# Sensor_Module_0x02_Temperature_Humidity_.net
KiCad netlist of a schematic drawn in EAGLE
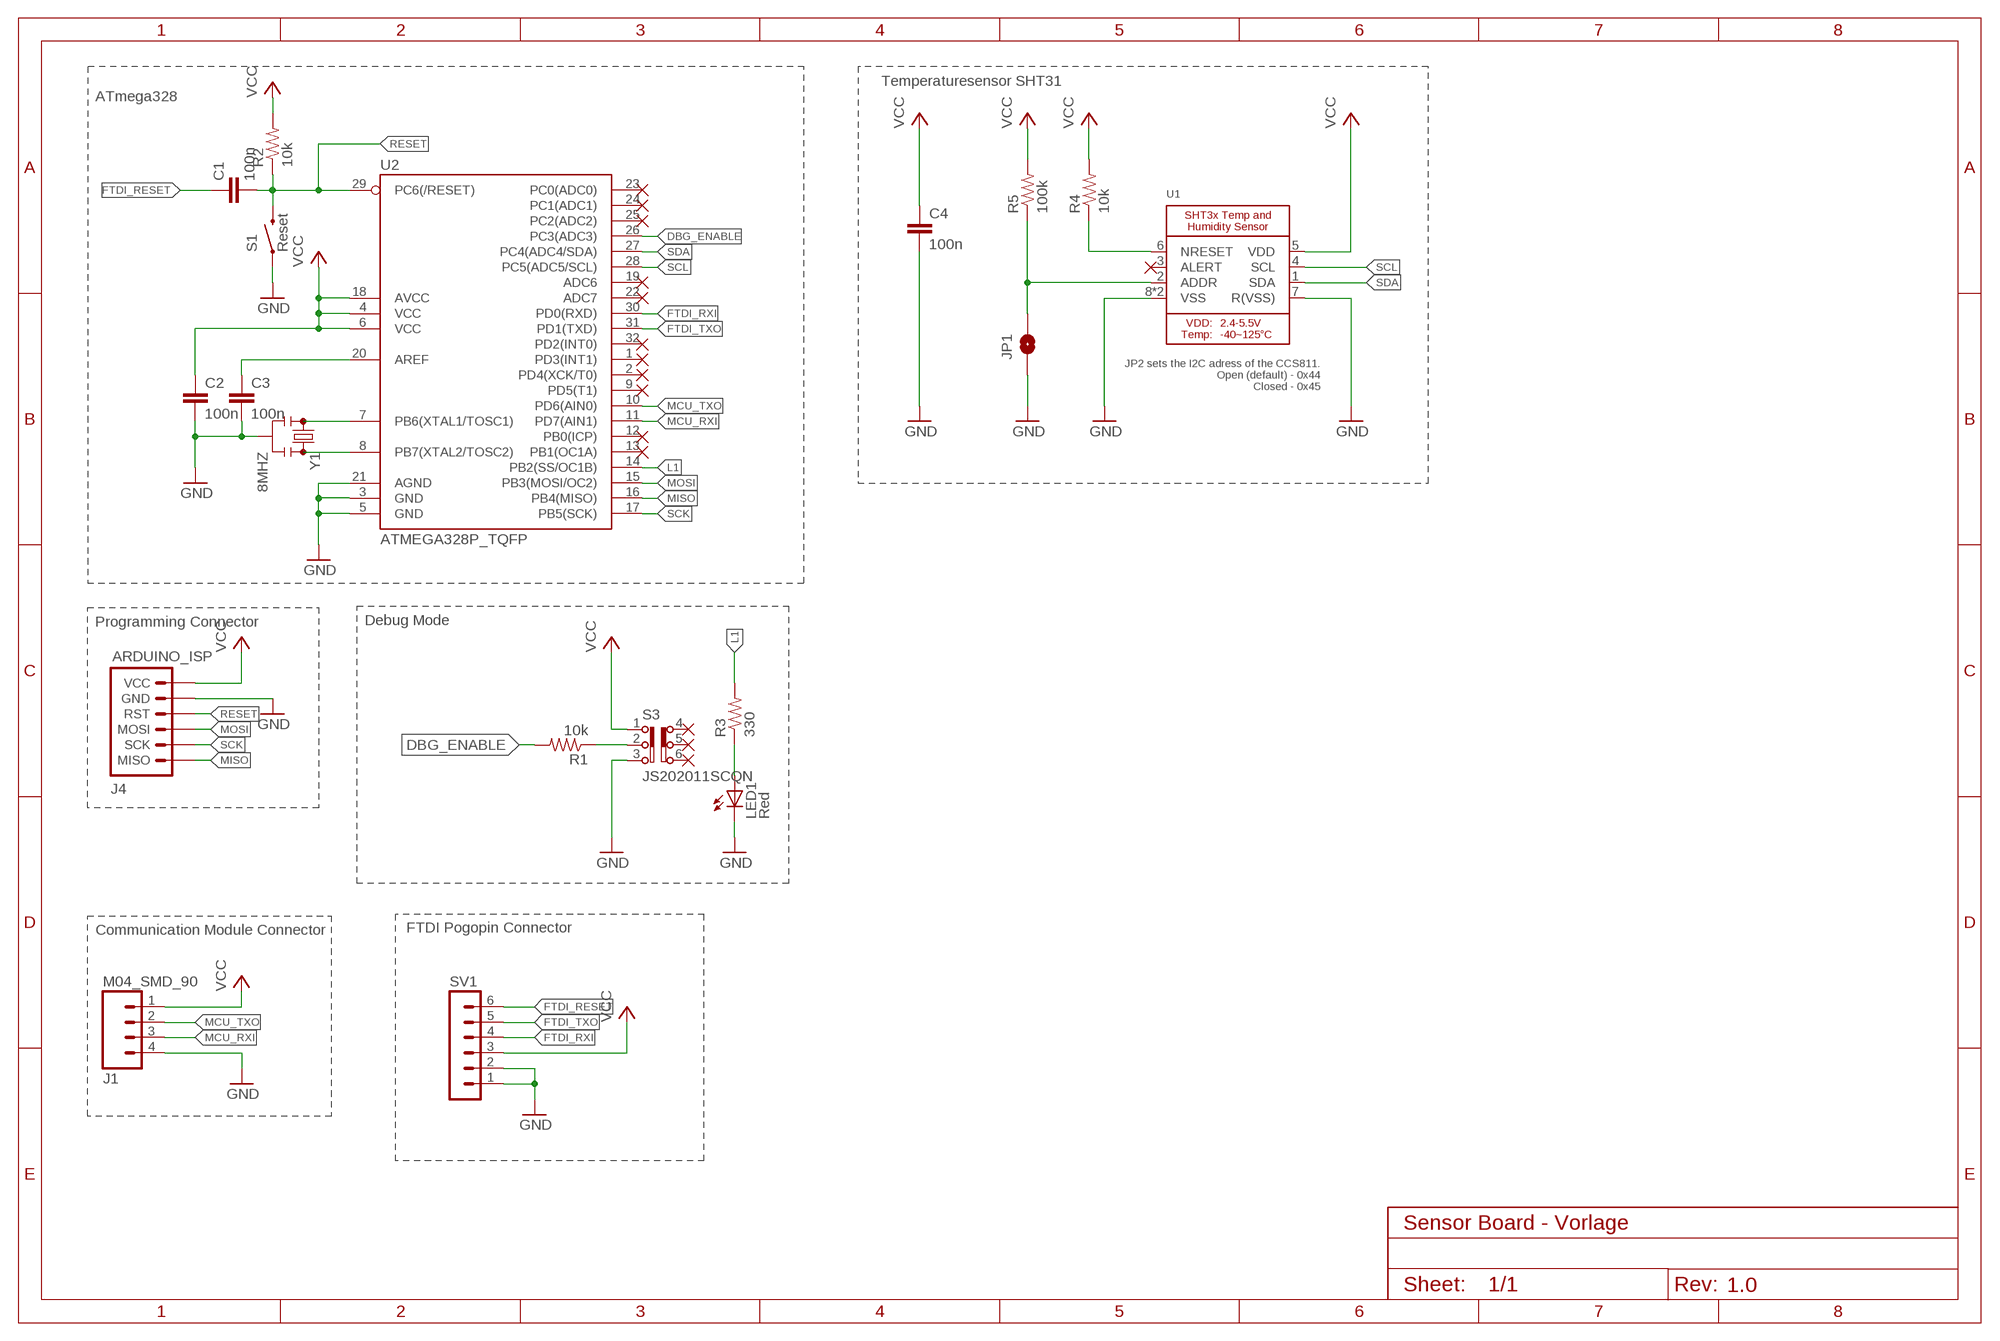
[diagram p0: schematic, sheet 1]

(export (version "E")
  (design (tool "Eeschema 10.0.6"))
  (components
    (comp (ref "C1")
      (value "100n")
      (footprint "eagle-import:C0805")
      (libsource (lib "eagle-import") (part "C"))
    )
    (comp (ref "C2")
      (value "100n")
      (footprint "eagle-import:C0805")
      (libsource (lib "eagle-import") (part "C"))
    )
    (comp (ref "C3")
      (value "100n")
      (footprint "eagle-import:C0805")
      (libsource (lib "eagle-import") (part "C"))
    )
    (comp (ref "C4")
      (value "100n")
      (footprint "eagle-import:C0805")
      (libsource (lib "eagle-import") (part "C"))
    )
    (comp (ref "J1")
      (value "M04_SMD_90")
      (footprint "eagle-import:M04_SMD_90")
      (libsource (lib "eagle-import") (part "M04_SMD_90"))
    )
    (comp (ref "J4")
      (value "ARDUINO_ISP")
      (footprint "eagle-import:M-2X3")
      (libsource (lib "eagle-import") (part "ARDUINO_ISP"))
    )
    (comp (ref "JP1")
      (value "SPARKFUN-JUMPERS_JUMPER-SMT_2_NO_SILK")
      (footprint "eagle-import:SPARKFUN-JUMPERS_SMT-JUMPER_2_NO_SILK")
      (libsource (lib "eagle-import") (part "SPARKFUN-JUMPERS_JUMPER-SMT_2_NO_SILK"))
    )
    (comp (ref "LED1")
      (value "Red")
      (footprint "eagle-import:SML0805")
      (libsource (lib "eagle-import") (part "LEDSML0805"))
    )
    (comp (ref "R1")
      (value "10k")
      (footprint "eagle-import:0805")
      (libsource (lib "eagle-import") (part "RESISTOR0805-RES"))
    )
    (comp (ref "R2")
      (value "10k")
      (footprint "eagle-import:0805")
      (libsource (lib "eagle-import") (part "RESISTOR0805-RES"))
    )
    (comp (ref "R3")
      (value "330")
      (footprint "eagle-import:0805")
      (libsource (lib "eagle-import") (part "RESISTOR0805-RES"))
    )
    (comp (ref "R4")
      (value "10k")
      (footprint "eagle-import:0805")
      (libsource (lib "eagle-import") (part "RESISTOR0805-RES"))
    )
    (comp (ref "R5")
      (value "100k")
      (footprint "eagle-import:0805")
      (libsource (lib "eagle-import") (part "RESISTOR0805-RES"))
    )
    (comp (ref "S1")
      (value "Reset")
      (footprint "eagle-import:M-PUSHBUTTON-SMD")
      (libsource (lib "eagle-import") (part "PUSHBUTTON"))
    )
    (comp (ref "S3")
      (value "JS202011SCQN")
      (footprint "eagle-import:JS202011SCQN")
      (libsource (lib "eagle-import") (part "JS202011SCQN"))
    )
    (comp (ref "SV1")
      (value "MA06-1")
      (footprint "eagle-import:MA06-1")
      (libsource (lib "eagle-import") (part "MA06-1"))
    )
    (comp (ref "U1")
      (value "MICROBUILDER_SHT3X")
      (footprint "eagle-import:MICROBUILDER_SHT3X")
      (libsource (lib "eagle-import") (part "MICROBUILDER_SHT3X"))
    )
    (comp (ref "U2")
      (value "ATMEGA328P_TQFP")
      (footprint "eagle-import:TQFP32-08")
      (libsource (lib "eagle-import") (part "ATMEGA328P_TQFP"))
    )
    (comp (ref "Y1")
      (value "8MHZ")
      (footprint "eagle-import:RESONATOR-SMD")
      (libsource (lib "eagle-import") (part "RESONATOR8MHZ"))
    )
  )
  (nets
    (net (code "1") (name "DBG_ENABLE") (class "Default")
      (node (ref "R1") (pin "2") (pinfunction "2_2") (pintype "passive"))
      (node (ref "U2") (pin "26") (pinfunction "PC3(ADC3)_26") (pintype "bidirectional"))
    )
    (net (code "2") (name "FTDI_RESET") (class "Default")
      (node (ref "C1") (pin "1") (pinfunction "1_1") (pintype "passive"))
      (node (ref "SV1") (pin "6") (pinfunction "6_6") (pintype "passive"))
    )
    (net (code "3") (name "FTDI_RXI") (class "Default")
      (node (ref "SV1") (pin "4") (pinfunction "4_4") (pintype "passive"))
      (node (ref "U2") (pin "30") (pinfunction "PD0(RXD)_30") (pintype "bidirectional"))
    )
    (net (code "4") (name "FTDI_TXO") (class "Default")
      (node (ref "SV1") (pin "5") (pinfunction "5_5") (pintype "passive"))
      (node (ref "U2") (pin "31") (pinfunction "PD1(TXD)_31") (pintype "bidirectional"))
    )
    (net (code "5") (name "GND") (class "Default")
      (node (ref "C2") (pin "2") (pinfunction "2_2") (pintype "passive"))
      (node (ref "C3") (pin "2") (pinfunction "2_2") (pintype "passive"))
      (node (ref "C4") (pin "2") (pinfunction "2_2") (pintype "passive"))
      (node (ref "J1") (pin "4") (pinfunction "4_4") (pintype "passive"))
      (node (ref "J4") (pin "P$5") (pinfunction "GND_P$5") (pintype "passive"))
      (node (ref "JP1") (pin "1") (pinfunction "1_1") (pintype "passive"))
      (node (ref "LED1") (pin "C") (pinfunction "C_C") (pintype "passive"))
      (node (ref "S1") (pin "1") (pinfunction "LEFT_1") (pintype "passive"))
      (node (ref "S1") (pin "2") (pinfunction "LEFT_2") (pintype "passive"))
      (node (ref "S3") (pin "3") (pinfunction "3_3") (pintype "passive"))
      (node (ref "SV1") (pin "1") (pinfunction "1_1") (pintype "passive"))
      (node (ref "SV1") (pin "2") (pinfunction "2_2") (pintype "passive"))
      (node (ref "U1") (pin "7") (pinfunction "R(VSS)_7") (pintype "bidirectional"))
      (node (ref "U1") (pin "8") (pinfunction "VSS_8") (pintype "power_in"))
      (node (ref "U1") (pin "THERMAL") (pinfunction "VSS_THERMAL") (pintype "power_in"))
      (node (ref "U2") (pin "21") (pinfunction "AGND_21") (pintype "bidirectional"))
      (node (ref "U2") (pin "3") (pinfunction "GND_3") (pintype "bidirectional"))
      (node (ref "U2") (pin "5") (pinfunction "GND_5") (pintype "bidirectional"))
      (node (ref "Y1") (pin "2") (pinfunction "2_2") (pintype "passive"))
    )
    (net (code "6") (name "L1") (class "Default")
      (node (ref "R3") (pin "2") (pinfunction "2_2") (pintype "passive"))
      (node (ref "U2") (pin "14") (pinfunction "PB2(SS/OC1B)_14") (pintype "bidirectional"))
    )
    (net (code "7") (name "MCU_RXI") (class "Default")
      (node (ref "J1") (pin "3") (pinfunction "3_3") (pintype "passive"))
      (node (ref "U2") (pin "11") (pinfunction "PD7(AIN1)_11") (pintype "bidirectional"))
    )
    (net (code "8") (name "MCU_TXO") (class "Default")
      (node (ref "J1") (pin "2") (pinfunction "2_2") (pintype "passive"))
      (node (ref "U2") (pin "10") (pinfunction "PD6(AIN0)_10") (pintype "bidirectional"))
    )
    (net (code "9") (name "MISO") (class "Default")
      (node (ref "J4") (pin "P$1") (pinfunction "MISO_P$1") (pintype "passive"))
      (node (ref "U2") (pin "16") (pinfunction "PB4(MISO)_16") (pintype "bidirectional"))
    )
    (net (code "10") (name "MOSI") (class "Default")
      (node (ref "J4") (pin "P$3") (pinfunction "MOSI_P$3") (pintype "passive"))
      (node (ref "U2") (pin "15") (pinfunction "PB3(MOSI/OC2)_15") (pintype "bidirectional"))
    )
    (net (code "11") (name "Net-(LED1-PadA)") (class "Default")
      (node (ref "LED1") (pin "A") (pinfunction "A_A") (pintype "passive"))
      (node (ref "R3") (pin "1") (pinfunction "1_1") (pintype "passive"))
    )
    (net (code "12") (name "Net-(R1-Pad1)") (class "Default")
      (node (ref "R1") (pin "1") (pinfunction "1_1") (pintype "passive"))
      (node (ref "S3") (pin "2") (pinfunction "2_2") (pintype "passive"))
    )
    (net (code "13") (name "Net-(U1-ADDR)") (class "Default")
      (node (ref "JP1") (pin "2") (pinfunction "2_2") (pintype "passive"))
      (node (ref "R5") (pin "1") (pinfunction "1_1") (pintype "passive"))
      (node (ref "U1") (pin "2") (pinfunction "ADDR_2") (pintype "bidirectional"))
    )
    (net (code "14") (name "Net-(U1-NRESET)") (class "Default")
      (node (ref "R4") (pin "1") (pinfunction "1_1") (pintype "passive"))
      (node (ref "U1") (pin "6") (pinfunction "NRESET_6") (pintype "bidirectional"))
    )
    (net (code "15") (name "Net-(U2-AREF)") (class "Default")
      (node (ref "C3") (pin "1") (pinfunction "1_1") (pintype "passive"))
      (node (ref "U2") (pin "20") (pinfunction "AREF_20") (pintype "bidirectional"))
    )
    (net (code "16") (name "Net-(U2-PB6(XTAL1{slash}TOSC1))") (class "Default")
      (node (ref "U2") (pin "7") (pinfunction "PB6(XTAL1/TOSC1)_7") (pintype "bidirectional"))
      (node (ref "Y1") (pin "1") (pinfunction "1_1") (pintype "passive"))
    )
    (net (code "17") (name "Net-(U2-PB7(XTAL2{slash}TOSC2))") (class "Default")
      (node (ref "U2") (pin "8") (pinfunction "PB7(XTAL2/TOSC2)_8") (pintype "bidirectional"))
      (node (ref "Y1") (pin "3") (pinfunction "3_3") (pintype "passive"))
    )
    (net (code "18") (name "RESET") (class "Default")
      (node (ref "C1") (pin "2") (pinfunction "2_2") (pintype "passive"))
      (node (ref "J4") (pin "P$4") (pinfunction "RST_P$4") (pintype "passive"))
      (node (ref "R2") (pin "1") (pinfunction "1_1") (pintype "passive"))
      (node (ref "S1") (pin "3") (pinfunction "RIGHT_3") (pintype "passive"))
      (node (ref "S1") (pin "4") (pinfunction "RIGHT_4") (pintype "passive"))
      (node (ref "U2") (pin "29") (pinfunction "PC6(/RESET)_29") (pintype "bidirectional"))
    )
    (net (code "19") (name "SCK") (class "Default")
      (node (ref "J4") (pin "P$2") (pinfunction "SCK_P$2") (pintype "passive"))
      (node (ref "U2") (pin "17") (pinfunction "PB5(SCK)_17") (pintype "bidirectional"))
    )
    (net (code "20") (name "SCL") (class "Default")
      (node (ref "U1") (pin "4") (pinfunction "SCL_4") (pintype "bidirectional"))
      (node (ref "U2") (pin "28") (pinfunction "PC5(ADC5/SCL)_28") (pintype "bidirectional"))
    )
    (net (code "21") (name "SDA") (class "Default")
      (node (ref "U1") (pin "1") (pinfunction "SDA_1") (pintype "bidirectional"))
      (node (ref "U2") (pin "27") (pinfunction "PC4(ADC4/SDA)_27") (pintype "bidirectional"))
    )
    (net (code "22") (name "VCC") (class "Default")
      (node (ref "C2") (pin "1") (pinfunction "1_1") (pintype "passive"))
      (node (ref "C4") (pin "1") (pinfunction "1_1") (pintype "passive"))
      (node (ref "J1") (pin "1") (pinfunction "1_1") (pintype "passive"))
      (node (ref "J4") (pin "P$6") (pinfunction "VCC_P$6") (pintype "passive"))
      (node (ref "R2") (pin "2") (pinfunction "2_2") (pintype "passive"))
      (node (ref "R4") (pin "2") (pinfunction "2_2") (pintype "passive"))
      (node (ref "R5") (pin "2") (pinfunction "2_2") (pintype "passive"))
      (node (ref "S3") (pin "1") (pinfunction "1_1") (pintype "passive"))
      (node (ref "SV1") (pin "3") (pinfunction "3_3") (pintype "passive"))
      (node (ref "U1") (pin "5") (pinfunction "VDD_5") (pintype "power_in"))
      (node (ref "U2") (pin "18") (pinfunction "AVCC_18") (pintype "bidirectional"))
      (node (ref "U2") (pin "4") (pinfunction "VCC_4") (pintype "bidirectional"))
      (node (ref "U2") (pin "6") (pinfunction "VCC_6") (pintype "bidirectional"))
    )
    (net (code "23") (name "unconnected-(S3-Pad4)") (class "Default")
      (node (ref "S3") (pin "4") (pinfunction "4_4") (pintype "passive"))
    )
    (net (code "24") (name "unconnected-(S3-Pad5)") (class "Default")
      (node (ref "S3") (pin "5") (pinfunction "5_5") (pintype "passive"))
    )
    (net (code "25") (name "unconnected-(S3-Pad6)") (class "Default")
      (node (ref "S3") (pin "6") (pinfunction "6_6") (pintype "passive"))
    )
    (net (code "26") (name "unconnected-(U1-ALERT-Pad3)") (class "Default")
      (node (ref "U1") (pin "3") (pinfunction "ALERT_3") (pintype "bidirectional"))
    )
    (net (code "27") (name "unconnected-(U2-ADC6-Pad19)") (class "Default")
      (node (ref "U2") (pin "19") (pinfunction "ADC6_19") (pintype "bidirectional"))
    )
    (net (code "28") (name "unconnected-(U2-ADC7-Pad22)") (class "Default")
      (node (ref "U2") (pin "22") (pinfunction "ADC7_22") (pintype "bidirectional"))
    )
    (net (code "29") (name "unconnected-(U2-PB0(ICP)-Pad12)") (class "Default")
      (node (ref "U2") (pin "12") (pinfunction "PB0(ICP)_12") (pintype "bidirectional"))
    )
    (net (code "30") (name "unconnected-(U2-PB1(OC1A)-Pad13)") (class "Default")
      (node (ref "U2") (pin "13") (pinfunction "PB1(OC1A)_13") (pintype "bidirectional"))
    )
    (net (code "31") (name "unconnected-(U2-PC0(ADC0)-Pad23)") (class "Default")
      (node (ref "U2") (pin "23") (pinfunction "PC0(ADC0)_23") (pintype "bidirectional"))
    )
    (net (code "32") (name "unconnected-(U2-PC1(ADC1)-Pad24)") (class "Default")
      (node (ref "U2") (pin "24") (pinfunction "PC1(ADC1)_24") (pintype "bidirectional"))
    )
    (net (code "33") (name "unconnected-(U2-PC2(ADC2)-Pad25)") (class "Default")
      (node (ref "U2") (pin "25") (pinfunction "PC2(ADC2)_25") (pintype "bidirectional"))
    )
    (net (code "34") (name "unconnected-(U2-PD2(INT0)-Pad32)") (class "Default")
      (node (ref "U2") (pin "32") (pinfunction "PD2(INT0)_32") (pintype "bidirectional"))
    )
    (net (code "35") (name "unconnected-(U2-PD3(INT1)-Pad1)") (class "Default")
      (node (ref "U2") (pin "1") (pinfunction "PD3(INT1)_1") (pintype "bidirectional"))
    )
    (net (code "36") (name "unconnected-(U2-PD4(XCK{slash}T0)-Pad2)") (class "Default")
      (node (ref "U2") (pin "2") (pinfunction "PD4(XCK/T0)_2") (pintype "bidirectional"))
    )
    (net (code "37") (name "unconnected-(U2-PD5(T1)-Pad9)") (class "Default")
      (node (ref "U2") (pin "9") (pinfunction "PD5(T1)_9") (pintype "bidirectional"))
    )
  )
)
